# design.net
KiCad netlist of a schematic drawn in Altium Designer
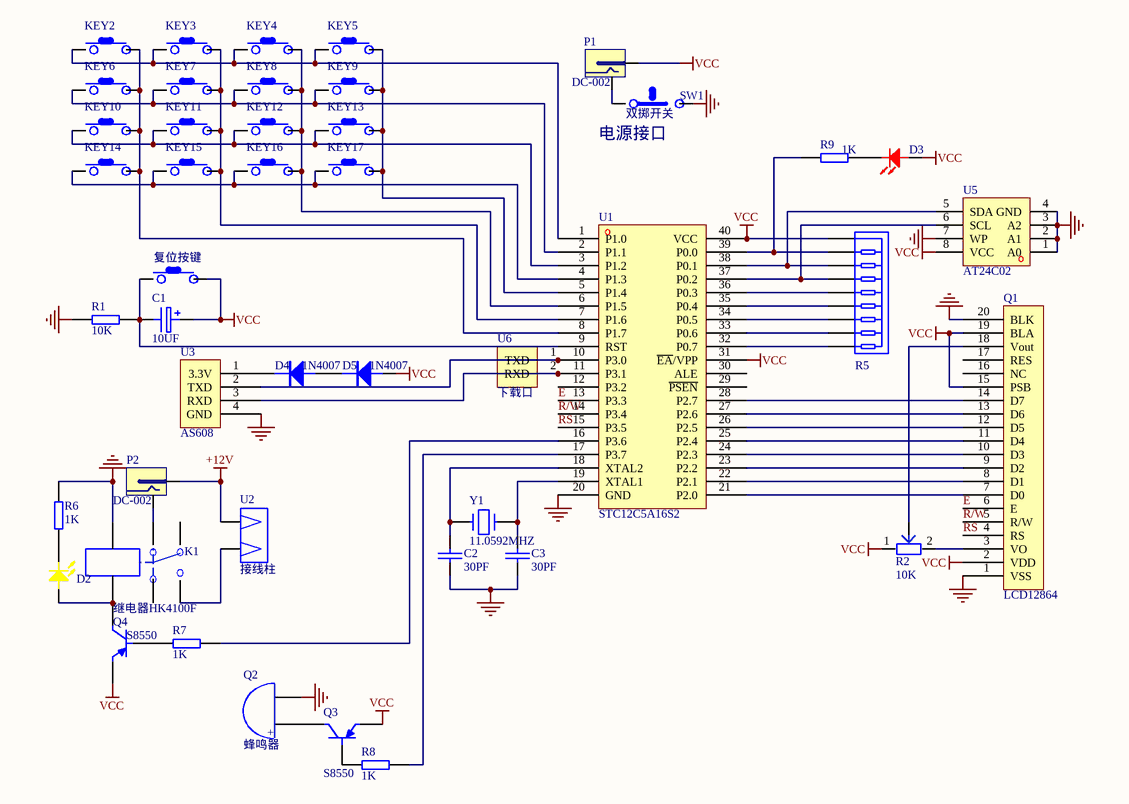
[diagram p0: 考勤机指纹密码锁部分原理图.SchDoc]

(export (version "E")
  (design (tool "Eeschema 10.0.6"))
  (components
    (comp (ref "C1") (value "10UF") (footprint "CD4") (libsource (lib "元件库") (part "电解电容")))
    (comp (ref "C2") (value "30PF") (footprint "R38") (libsource (lib "元件库") (part "瓷片电容")))
    (comp (ref "C3") (value "30PF") (footprint "R38") (libsource (lib "元件库") (part "瓷片电容")))
    (comp (ref "D2")
      (value "LED-YELLOW")
      (footprint "LED-YELLOW")
      (libsource (lib "元件库") (part "LED-YELLOW"))
    )
    (comp (ref "D3") (value "LED-RED") (footprint "LED-RED") (libsource (lib "元件库") (part "LED-RED")))
    (comp (ref "D4") (value "1N4007") (footprint "DO-41") (libsource (lib "元件库") (part "1N4007")))
    (comp (ref "D5") (value "1N4007") (footprint "DO-41") (libsource (lib "元件库") (part "1N4007")))
    (comp (ref "K1") (value "继电器HK4100F") (footprint "HK4100F") (libsource (lib "元件库") (part "继电器HK4100F")))
    (comp (ref "KEY1") (value "复位按键") (footprint "SW") (libsource (lib "元件库") (part "微动开关")))
    (comp (ref "KEY2") (value "复位按键") (footprint "SW") (libsource (lib "元件库") (part "微动开关")))
    (comp (ref "KEY3") (value "复位按键") (footprint "SW") (libsource (lib "元件库") (part "微动开关")))
    (comp (ref "KEY4") (value "复位按键") (footprint "SW") (libsource (lib "元件库") (part "微动开关")))
    (comp (ref "KEY5") (value "复位按键") (footprint "SW") (libsource (lib "元件库") (part "微动开关")))
    (comp (ref "KEY6") (value "复位按键") (footprint "SW") (libsource (lib "元件库") (part "微动开关")))
    (comp (ref "KEY7") (value "复位按键") (footprint "SW") (libsource (lib "元件库") (part "微动开关")))
    (comp (ref "KEY8") (value "复位按键") (footprint "SW") (libsource (lib "元件库") (part "微动开关")))
    (comp (ref "KEY9") (value "复位按键") (footprint "SW") (libsource (lib "元件库") (part "微动开关")))
    (comp (ref "KEY10") (value "复位按键") (footprint "SW") (libsource (lib "元件库") (part "微动开关")))
    (comp (ref "KEY11") (value "复位按键") (footprint "SW") (libsource (lib "元件库") (part "微动开关")))
    (comp (ref "KEY12") (value "复位按键") (footprint "SW") (libsource (lib "元件库") (part "微动开关")))
    (comp (ref "KEY13") (value "复位按键") (footprint "SW") (libsource (lib "元件库") (part "微动开关")))
    (comp (ref "KEY14") (value "复位按键") (footprint "SW") (libsource (lib "元件库") (part "微动开关")))
    (comp (ref "KEY15") (value "复位按键") (footprint "SW") (libsource (lib "元件库") (part "微动开关")))
    (comp (ref "KEY16") (value "复位按键") (footprint "SW") (libsource (lib "元件库") (part "微动开关")))
    (comp (ref "KEY17") (value "复位按键") (footprint "SW") (libsource (lib "元件库") (part "微动开关")))
    (comp (ref "P1") (value "DC-002") (footprint "DC-002") (libsource (lib "元件库") (part "DC-002")))
    (comp (ref "P2") (value "DC-002") (footprint "DC-005") (libsource (lib "元件库") (part "DC-002")))
    (comp (ref "Q1") (value "LCD12864") (footprint "HDR20") (libsource (lib "元件库") (part "LCD12864")))
    (comp (ref "Q2") (value "蜂鸣器") (footprint "蜂鸣器") (libsource (lib "元件库") (part "蜂鸣器")))
    (comp (ref "Q3") (value "S8550") (footprint "三极管") (libsource (lib "元件库") (part "S8550")))
    (comp (ref "Q4") (value "S8550") (footprint "三极管") (libsource (lib "元件库") (part "S8550")))
    (comp (ref "R1") (value "10K") (footprint "AXIAL-0.4") (libsource (lib "元件库") (part "RES")))
    (comp (ref "R2") (value "10K") (footprint "Res-JT") (libsource (lib "元件库") (part "电位器")))
    (comp (ref "R5") (value "10k") (footprint "R*9") (libsource (lib "元件库") (part "排阻")))
    (comp (ref "R6") (value "1K") (footprint "AXIAL-0.3") (libsource (lib "元件库") (part "RES")))
    (comp (ref "R7") (value "1K") (footprint "AXIAL-0.3") (libsource (lib "元件库") (part "RES")))
    (comp (ref "R8") (value "1K") (footprint "AXIAL-0.3") (libsource (lib "元件库") (part "RES")))
    (comp (ref "R9") (value "1K") (footprint "AXIAL-0.3") (libsource (lib "元件库") (part "RES")))
    (comp (ref "SW1") (value "双掷开关") (footprint "SS12D07G5") (libsource (lib "元件库") (part "双掷开关")))
    (comp (ref "U1") (value "STC12C5A16S2") (footprint "DIP40") (libsource (lib "元件库") (part "STC89C52")))
    (comp (ref "U2") (value "接线柱") (footprint "XH2P") (libsource (lib "元件库") (part "接线柱")))
    (comp (ref "U3") (value "AS608") (footprint "XH4P") (libsource (lib "元件库") (part "AS608")))
    (comp (ref "U5") (value "AT24C02") (footprint "DIP8") (libsource (lib "元件库") (part "AT24C02")))
    (comp (ref "U6") (value "下载口") (footprint "HDR2") (libsource (lib "元件库") (part "下载口")))
    (comp (ref "Y1") (value "11.0592MHZ") (footprint "XTAL") (libsource (lib "元件库") (part "XTAL")))
  )
  (nets
    (net (code "1") (name "+12V") (class "Default")
      (node (ref "P2") (pin "1") (pinfunction "1_1") (pintype "passive"))
      (node (ref "U2") (pin "2") (pinfunction "2_2") (pintype "passive"))
    )
    (net (code "2") (name "/E") (class "Default")
      (node (ref "Q1") (pin "6") (pinfunction "E_6") (pintype "passive"))
      (node (ref "U1") (pin "13") (pinfunction "P3.3_13") (pintype "passive"))
    )
    (net (code "3") (name "/RS") (class "Default")
      (node (ref "Q1") (pin "4") (pinfunction "RS_4") (pintype "passive"))
      (node (ref "U1") (pin "15") (pinfunction "P3.5_15") (pintype "passive"))
    )
    (net (code "4") (name "/R{slash}W") (class "Default")
      (node (ref "Q1") (pin "5") (pinfunction "R/W_5") (pintype "passive"))
      (node (ref "U1") (pin "14") (pinfunction "P3.4_14") (pintype "passive"))
    )
    (net (code "5") (name "GND") (class "Default")
      (node (ref "C2") (pin "2") (pinfunction "2_2") (pintype "passive"))
      (node (ref "C3") (pin "1") (pinfunction "1_1") (pintype "passive"))
      (node (ref "K1") (pin "5") (pinfunction "5_5") (pintype "passive"))
      (node (ref "Q1") (pin "1") (pinfunction "VSS_1") (pintype "passive"))
      (node (ref "Q1") (pin "20") (pinfunction "BLK_20") (pintype "passive"))
      (node (ref "Q2") (pin "2") (pinfunction "2_2") (pintype "passive"))
      (node (ref "R1") (pin "1") (pinfunction "1_1") (pintype "passive"))
      (node (ref "R6") (pin "1") (pinfunction "1_1") (pintype "passive"))
      (node (ref "SW1") (pin "2") (pinfunction "2_2") (pintype "passive"))
      (node (ref "U1") (pin "20") (pinfunction "GND_20") (pintype "passive"))
      (node (ref "U3") (pin "4") (pinfunction "GND_4") (pintype "passive"))
      (node (ref "U5") (pin "1") (pinfunction "A0_1") (pintype "passive"))
      (node (ref "U5") (pin "2") (pinfunction "A1_2") (pintype "passive"))
      (node (ref "U5") (pin "3") (pinfunction "A2_3") (pintype "passive"))
      (node (ref "U5") (pin "4") (pinfunction "GND_4") (pintype "passive"))
      (node (ref "U5") (pin "7") (pinfunction "WP_7") (pintype "passive"))
    )
    (net (code "6") (name "Net-(C1-E)") (class "Default")
      (node (ref "C1") (pin "2") (pinfunction "E_2") (pintype "passive"))
      (node (ref "KEY1") (pin "1") (pinfunction "3_1") (pintype "passive"))
      (node (ref "R1") (pin "2") (pinfunction "2_2") (pintype "passive"))
      (node (ref "U1") (pin "9") (pinfunction "RST_9") (pintype "passive"))
    )
    (net (code "7") (name "Net-(D2-Pad2)") (class "Default")
      (node (ref "D2") (pin "2") (pintype "passive"))
      (node (ref "R6") (pin "2") (pinfunction "2_2") (pintype "passive"))
    )
    (net (code "8") (name "Net-(D3-Pad2)") (class "Default")
      (node (ref "D3") (pin "2") (pintype "passive"))
      (node (ref "R9") (pin "1") (pinfunction "1_1") (pintype "passive"))
    )
    (net (code "9") (name "Net-(D4-Pad1)") (class "Default")
      (node (ref "D4") (pin "1") (pintype "passive"))
      (node (ref "D5") (pin "2") (pintype "passive"))
    )
    (net (code "10") (name "Net-(K1-Pad4)") (class "Default")
      (node (ref "K1") (pin "4") (pinfunction "4_4") (pintype "passive"))
      (node (ref "U2") (pin "1") (pinfunction "1_1") (pintype "passive"))
    )
    (net (code "11") (name "Net-(K1-Pad6)") (class "Default")
      (node (ref "K1") (pin "6") (pinfunction "6_6") (pintype "passive"))
      (node (ref "P2") (pin "2") (pinfunction "2_2") (pintype "passive"))
    )
    (net (code "12") (name "Net-(KEY2-3)") (class "Default")
      (node (ref "KEY2") (pin "1") (pinfunction "3_1") (pintype "passive"))
      (node (ref "KEY3") (pin "1") (pinfunction "3_1") (pintype "passive"))
      (node (ref "KEY4") (pin "1") (pinfunction "3_1") (pintype "passive"))
      (node (ref "KEY5") (pin "1") (pinfunction "3_1") (pintype "passive"))
      (node (ref "U1") (pin "1") (pinfunction "P1.0_1") (pintype "passive"))
    )
    (net (code "13") (name "Net-(KEY6-3)") (class "Default")
      (node (ref "KEY6") (pin "1") (pinfunction "3_1") (pintype "passive"))
      (node (ref "KEY7") (pin "1") (pinfunction "3_1") (pintype "passive"))
      (node (ref "KEY8") (pin "1") (pinfunction "3_1") (pintype "passive"))
      (node (ref "KEY9") (pin "1") (pinfunction "3_1") (pintype "passive"))
      (node (ref "U1") (pin "2") (pinfunction "P1.1_2") (pintype "passive"))
    )
    (net (code "14") (name "Net-(KEY10-3)") (class "Default")
      (node (ref "KEY10") (pin "1") (pinfunction "3_1") (pintype "passive"))
      (node (ref "KEY11") (pin "1") (pinfunction "3_1") (pintype "passive"))
      (node (ref "KEY12") (pin "1") (pinfunction "3_1") (pintype "passive"))
      (node (ref "KEY13") (pin "1") (pinfunction "3_1") (pintype "passive"))
      (node (ref "U1") (pin "3") (pinfunction "P1.2_3") (pintype "passive"))
    )
    (net (code "15") (name "Net-(KEY10-4)") (class "Default")
      (node (ref "KEY10") (pin "2") (pinfunction "4_2") (pintype "passive"))
      (node (ref "KEY14") (pin "2") (pinfunction "4_2") (pintype "passive"))
      (node (ref "KEY2") (pin "2") (pinfunction "4_2") (pintype "passive"))
      (node (ref "KEY6") (pin "2") (pinfunction "4_2") (pintype "passive"))
      (node (ref "U1") (pin "8") (pinfunction "P1.7_8") (pintype "passive"))
    )
    (net (code "16") (name "Net-(KEY11-4)") (class "Default")
      (node (ref "KEY11") (pin "2") (pinfunction "4_2") (pintype "passive"))
      (node (ref "KEY15") (pin "2") (pinfunction "4_2") (pintype "passive"))
      (node (ref "KEY3") (pin "2") (pinfunction "4_2") (pintype "passive"))
      (node (ref "KEY7") (pin "2") (pinfunction "4_2") (pintype "passive"))
      (node (ref "U1") (pin "7") (pinfunction "P1.6_7") (pintype "passive"))
    )
    (net (code "17") (name "Net-(KEY12-4)") (class "Default")
      (node (ref "KEY12") (pin "2") (pinfunction "4_2") (pintype "passive"))
      (node (ref "KEY16") (pin "2") (pinfunction "4_2") (pintype "passive"))
      (node (ref "KEY4") (pin "2") (pinfunction "4_2") (pintype "passive"))
      (node (ref "KEY8") (pin "2") (pinfunction "4_2") (pintype "passive"))
      (node (ref "U1") (pin "6") (pinfunction "P1.5_6") (pintype "passive"))
    )
    (net (code "18") (name "Net-(KEY13-4)") (class "Default")
      (node (ref "KEY13") (pin "2") (pinfunction "4_2") (pintype "passive"))
      (node (ref "KEY17") (pin "2") (pinfunction "4_2") (pintype "passive"))
      (node (ref "KEY5") (pin "2") (pinfunction "4_2") (pintype "passive"))
      (node (ref "KEY9") (pin "2") (pinfunction "4_2") (pintype "passive"))
      (node (ref "U1") (pin "5") (pinfunction "P1.4_5") (pintype "passive"))
    )
    (net (code "19") (name "Net-(KEY14-3)") (class "Default")
      (node (ref "KEY14") (pin "1") (pinfunction "3_1") (pintype "passive"))
      (node (ref "KEY15") (pin "1") (pinfunction "3_1") (pintype "passive"))
      (node (ref "KEY16") (pin "1") (pinfunction "3_1") (pintype "passive"))
      (node (ref "KEY17") (pin "1") (pinfunction "3_1") (pintype "passive"))
      (node (ref "U1") (pin "4") (pinfunction "P1.3_4") (pintype "passive"))
    )
    (net (code "20") (name "Net-(P1-Pad2)") (class "Default")
      (node (ref "P1") (pin "2") (pinfunction "2_2") (pintype "passive"))
      (node (ref "SW1") (pin "1") (pinfunction "1_1") (pintype "passive"))
    )
    (net (code "21") (name "Net-(Q1-D0)") (class "Default")
      (node (ref "Q1") (pin "7") (pinfunction "D0_7") (pintype "passive"))
      (node (ref "U1") (pin "21") (pinfunction "P2.0_21") (pintype "passive"))
    )
    (net (code "22") (name "Net-(Q1-D1)") (class "Default")
      (node (ref "Q1") (pin "8") (pinfunction "D1_8") (pintype "passive"))
      (node (ref "U1") (pin "22") (pinfunction "P2.1_22") (pintype "passive"))
    )
    (net (code "23") (name "Net-(Q1-D2)") (class "Default")
      (node (ref "Q1") (pin "9") (pinfunction "D2_9") (pintype "passive"))
      (node (ref "U1") (pin "23") (pinfunction "P2.2_23") (pintype "passive"))
    )
    (net (code "24") (name "Net-(Q1-D3)") (class "Default")
      (node (ref "Q1") (pin "10") (pinfunction "D3_10") (pintype "passive"))
      (node (ref "U1") (pin "24") (pinfunction "P2.3_24") (pintype "passive"))
    )
    (net (code "25") (name "Net-(Q1-D4)") (class "Default")
      (node (ref "Q1") (pin "11") (pinfunction "D4_11") (pintype "passive"))
      (node (ref "U1") (pin "25") (pinfunction "P2.4_25") (pintype "passive"))
    )
    (net (code "26") (name "Net-(Q1-D5)") (class "Default")
      (node (ref "Q1") (pin "12") (pinfunction "D5_12") (pintype "passive"))
      (node (ref "U1") (pin "26") (pinfunction "P2.5_26") (pintype "passive"))
    )
    (net (code "27") (name "Net-(Q1-D6)") (class "Default")
      (node (ref "Q1") (pin "13") (pinfunction "D6_13") (pintype "passive"))
      (node (ref "U1") (pin "27") (pinfunction "P2.6_27") (pintype "passive"))
    )
    (net (code "28") (name "Net-(Q1-D7)") (class "Default")
      (node (ref "Q1") (pin "14") (pinfunction "D7_14") (pintype "passive"))
      (node (ref "U1") (pin "28") (pinfunction "P2.7_28") (pintype "passive"))
    )
    (net (code "29") (name "Net-(Q1-VO)") (class "Default")
      (node (ref "Q1") (pin "3") (pinfunction "VO_3") (pintype "passive"))
      (node (ref "R2") (pin "2") (pinfunction "2_2") (pintype "passive"))
    )
    (net (code "30") (name "Net-(Q1-Vout)") (class "Default")
      (node (ref "Q1") (pin "18") (pinfunction "Vout_18") (pintype "passive"))
      (node (ref "R2") (pin "3") (pinfunction "3_3") (pintype "passive"))
    )
    (net (code "31") (name "Net-(Q3-B)") (class "Default")
      (node (ref "Q3") (pin "2") (pinfunction "B_2") (pintype "passive"))
      (node (ref "R8") (pin "1") (pinfunction "1_1") (pintype "passive"))
    )
    (net (code "32") (name "Net-(Q3-C)") (class "Default")
      (node (ref "Q2") (pin "1") (pinfunction "1_1") (pintype "passive"))
      (node (ref "Q3") (pin "3") (pinfunction "C_3") (pintype "passive"))
    )
    (net (code "33") (name "Net-(Q4-B)") (class "Default")
      (node (ref "Q4") (pin "2") (pinfunction "B_2") (pintype "passive"))
      (node (ref "R7") (pin "1") (pinfunction "1_1") (pintype "passive"))
    )
    (net (code "34") (name "Net-(Q4-C)") (class "Default")
      (node (ref "D2") (pin "1") (pintype "passive"))
      (node (ref "K1") (pin "2") (pinfunction "2_2") (pintype "passive"))
      (node (ref "Q4") (pin "3") (pinfunction "C_3") (pintype "passive"))
    )
    (net (code "35") (name "Net-(U1-P0.0)") (class "Default")
      (node (ref "R5") (pin "2") (pinfunction "2_2") (pintype "passive"))
      (node (ref "R9") (pin "2") (pinfunction "2_2") (pintype "passive"))
      (node (ref "U1") (pin "39") (pinfunction "P0.0_39") (pintype "passive"))
    )
    (net (code "36") (name "Net-(U1-P0.1)") (class "Default")
      (node (ref "R5") (pin "3") (pinfunction "3_3") (pintype "passive"))
      (node (ref "U1") (pin "38") (pinfunction "P0.1_38") (pintype "passive"))
      (node (ref "U5") (pin "5") (pinfunction "SDA_5") (pintype "passive"))
    )
    (net (code "37") (name "Net-(U1-P0.2)") (class "Default")
      (node (ref "R5") (pin "4") (pinfunction "4_4") (pintype "passive"))
      (node (ref "U1") (pin "37") (pinfunction "P0.2_37") (pintype "passive"))
      (node (ref "U5") (pin "6") (pinfunction "SCL_6") (pintype "passive"))
    )
    (net (code "38") (name "Net-(U1-P0.3)") (class "Default")
      (node (ref "R5") (pin "5") (pinfunction "5_5") (pintype "passive"))
      (node (ref "U1") (pin "36") (pinfunction "P0.3_36") (pintype "passive"))
    )
    (net (code "39") (name "Net-(U1-P0.4)") (class "Default")
      (node (ref "R5") (pin "6") (pinfunction "6_6") (pintype "passive"))
      (node (ref "U1") (pin "35") (pinfunction "P0.4_35") (pintype "passive"))
    )
    (net (code "40") (name "Net-(U1-P0.5)") (class "Default")
      (node (ref "R5") (pin "7") (pinfunction "7_7") (pintype "passive"))
      (node (ref "U1") (pin "34") (pinfunction "P0.5_34") (pintype "passive"))
    )
    (net (code "41") (name "Net-(U1-P0.6)") (class "Default")
      (node (ref "R5") (pin "8") (pinfunction "8_8") (pintype "passive"))
      (node (ref "U1") (pin "33") (pinfunction "P0.6_33") (pintype "passive"))
    )
    (net (code "42") (name "Net-(U1-P0.7)") (class "Default")
      (node (ref "R5") (pin "9") (pinfunction "9_9") (pintype "passive"))
      (node (ref "U1") (pin "32") (pinfunction "P0.7_32") (pintype "passive"))
    )
    (net (code "43") (name "Net-(U1-P3.0)") (class "Default")
      (node (ref "U1") (pin "10") (pinfunction "P3.0_10") (pintype "passive"))
      (node (ref "U3") (pin "2") (pinfunction "TXD_2") (pintype "passive"))
      (node (ref "U6") (pin "1") (pinfunction "TXD_1") (pintype "passive"))
    )
    (net (code "44") (name "Net-(U1-P3.1)") (class "Default")
      (node (ref "U1") (pin "11") (pinfunction "P3.1_11") (pintype "passive"))
      (node (ref "U3") (pin "3") (pinfunction "RXD_3") (pintype "passive"))
      (node (ref "U6") (pin "2") (pinfunction "RXD_2") (pintype "passive"))
    )
    (net (code "45") (name "Net-(U1-P3.6)") (class "Default")
      (node (ref "R7") (pin "2") (pinfunction "2_2") (pintype "passive"))
      (node (ref "U1") (pin "16") (pinfunction "P3.6_16") (pintype "passive"))
    )
    (net (code "46") (name "Net-(U1-P3.7)") (class "Default")
      (node (ref "R8") (pin "2") (pinfunction "2_2") (pintype "passive"))
      (node (ref "U1") (pin "17") (pinfunction "P3.7_17") (pintype "passive"))
    )
    (net (code "47") (name "Net-(U1-XTAL1)") (class "Default")
      (node (ref "C3") (pin "2") (pinfunction "2_2") (pintype "passive"))
      (node (ref "U1") (pin "19") (pinfunction "XTAL1_19") (pintype "passive"))
      (node (ref "Y1") (pin "1") (pinfunction "1_1") (pintype "passive"))
    )
    (net (code "48") (name "Net-(U1-XTAL2)") (class "Default")
      (node (ref "C2") (pin "1") (pinfunction "1_1") (pintype "passive"))
      (node (ref "U1") (pin "18") (pinfunction "XTAL2_18") (pintype "passive"))
      (node (ref "Y1") (pin "2") (pinfunction "2_2") (pintype "passive"))
    )
    (net (code "49") (name "Net-(U3-3.3V)") (class "Default")
      (node (ref "D4") (pin "2") (pintype "passive"))
      (node (ref "U3") (pin "1") (pinfunction "3.3V_1") (pintype "passive"))
    )
    (net (code "50") (name "VCC") (class "Default")
      (node (ref "C1") (pin "1") (pinfunction "1_1") (pintype "passive"))
      (node (ref "D3") (pin "1") (pintype "passive"))
      (node (ref "D5") (pin "1") (pintype "passive"))
      (node (ref "KEY1") (pin "2") (pinfunction "4_2") (pintype "passive"))
      (node (ref "P1") (pin "1") (pinfunction "1_1") (pintype "passive"))
      (node (ref "Q1") (pin "15") (pinfunction "PSB_15") (pintype "passive"))
      (node (ref "Q1") (pin "19") (pinfunction "BLA_19") (pintype "passive"))
      (node (ref "Q1") (pin "2") (pinfunction "VDD_2") (pintype "passive"))
      (node (ref "Q3") (pin "1") (pinfunction "E_1") (pintype "passive"))
      (node (ref "Q4") (pin "1") (pinfunction "E_1") (pintype "passive"))
      (node (ref "R2") (pin "1") (pinfunction "1_1") (pintype "passive"))
      (node (ref "R5") (pin "1") (pinfunction "1_1") (pintype "passive"))
      (node (ref "U1") (pin "31") (pinfunction "~{EA}/VPP_31") (pintype "passive"))
      (node (ref "U1") (pin "40") (pinfunction "VCC_40") (pintype "passive"))
      (node (ref "U5") (pin "8") (pinfunction "VCC_8") (pintype "passive"))
    )
    (net (code "51") (name "unconnected-(K1-Pad1)") (class "Default")
      (node (ref "K1") (pin "1") (pinfunction "1_1") (pintype "passive"))
    )
    (net (code "52") (name "unconnected-(K1-Pad3)") (class "Default")
      (node (ref "K1") (pin "3") (pinfunction "3_3") (pintype "passive"))
    )
    (net (code "53") (name "unconnected-(Q1-NC-Pad16)") (class "Default")
      (node (ref "Q1") (pin "16") (pinfunction "NC_16") (pintype "passive"))
    )
    (net (code "54") (name "unconnected-(Q1-RES-Pad17)") (class "Default")
      (node (ref "Q1") (pin "17") (pinfunction "RES_17") (pintype "passive"))
    )
    (net (code "55") (name "unconnected-(U1-ALE-Pad30)") (class "Default")
      (node (ref "U1") (pin "30") (pinfunction "ALE_30") (pintype "passive"))
    )
    (net (code "56") (name "unconnected-(U1-P3.2-Pad12)") (class "Default")
      (node (ref "U1") (pin "12") (pinfunction "P3.2_12") (pintype "passive"))
    )
    (net (code "57") (name "unconnected-(U1-~{PSEN}-Pad29)") (class "Default")
      (node (ref "U1") (pin "29") (pinfunction "~{PSEN}_29") (pintype "passive"))
    )
  )
)
